# PowerSupply.net
KiCad netlist of a schematic drawn in Altium Designer
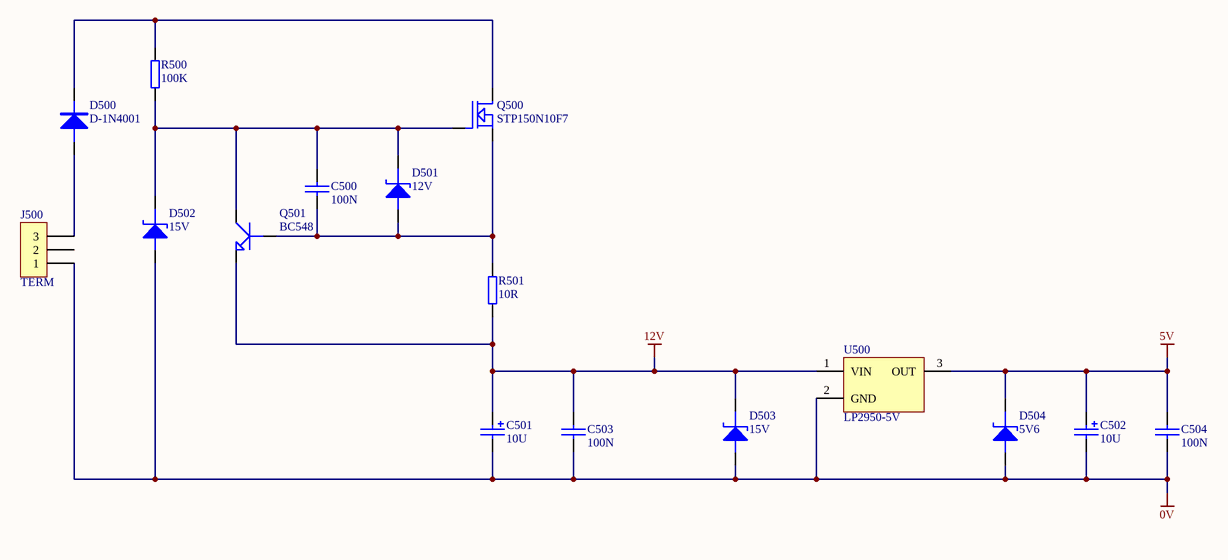
[diagram p0: PowerSupply.SchDoc]

(export (version "E")
  (design (tool "Eeschema 10.0.6"))
  (components
    (comp (ref "C500")
      (value "100N")
      (footprint "AXIAL02")
      (description "CAPACITOR")
      (libsource (lib "SSR") (part "C-B100N"))
    )
    (comp (ref "C501")
      (value "10U")
      (footprint "RADIAL02P")
      (description "CAP")
      (libsource (lib "SSR") (part "C-A10U"))
    )
    (comp (ref "C502")
      (value "10U")
      (footprint "RADIAL02P")
      (description "CAP")
      (libsource (lib "SSR") (part "C-A10U"))
    )
    (comp (ref "C503")
      (value "100N")
      (footprint "AXIAL02")
      (description "CAPACITOR")
      (libsource (lib "SSR") (part "C-B100N"))
    )
    (comp (ref "C504")
      (value "100N")
      (footprint "AXIAL02")
      (description "CAPACITOR")
      (libsource (lib "SSR") (part "C-B100N"))
    )
    (comp (ref "D500")
      (value "D-1N4001")
      (footprint "DO35S")
      (description "1N4001")
      (libsource (lib "SSR") (part "D-1N4001"))
    )
    (comp (ref "D501")
      (value "12V")
      (footprint "DO35S")
      (description "ZENER DIODE")
      (libsource (lib "SSR") (part "D-BZX79-12"))
    )
    (comp (ref "D502")
      (value "15V")
      (footprint "DO35S")
      (description "ZENER DIODE")
      (libsource (lib "SSR") (part "D-BZX79-15"))
    )
    (comp (ref "D503")
      (value "15V")
      (footprint "DO35S")
      (description "ZENER DIODE")
      (libsource (lib "SSR") (part "D-BZX79-15"))
    )
    (comp (ref "D504")
      (value "5V6")
      (footprint "DO35S")
      (description "ZENER DIODE")
      (libsource (lib "SSR") (part "D-BZX79-5V6"))
    )
    (comp (ref "J500")
      (value "TERM")
      (footprint "MKD500S3")
      (description "CONNECTOR")
      (libsource (lib "SSR") (part "J-SCR-3"))
    )
    (comp (ref "Q500")
      (value "STP150N10F7")
      (footprint "TO220FS")
      (description "MOSFET")
      (libsource (lib "SSR") (part "Q-STP150N10F7"))
    )
    (comp (ref "Q501") (value "BC548") (footprint "TO92") (libsource (lib "SSR") (part "Q-BC548")))
    (comp (ref "R500")
      (value "100K")
      (footprint "AXIAL04")
      (description "RESISTOR")
      (libsource (lib "SSR") (part "R-A100K"))
    )
    (comp (ref "R501")
      (value "10R")
      (footprint "AXIAL04")
      (description "RESISTOR")
      (libsource (lib "SSR") (part "R-A10R"))
    )
    (comp (ref "U500")
      (value "LP2950-5V")
      (footprint "TO92")
      (description "LP2950")
      (libsource (lib "SSR") (part "U-LP2950"))
    )
  )
  (nets
    (net (code "1") (name "0V") (class "Default")
      (node (ref "C501") (pin "2") (pinfunction "2_2") (pintype "passive"))
      (node (ref "C502") (pin "2") (pinfunction "2_2") (pintype "passive"))
      (node (ref "C503") (pin "2") (pinfunction "2_2") (pintype "passive"))
      (node (ref "C504") (pin "2") (pinfunction "2_2") (pintype "passive"))
      (node (ref "D502") (pin "1") (pinfunction "A_1") (pintype "passive"))
      (node (ref "D503") (pin "1") (pinfunction "A_1") (pintype "passive"))
      (node (ref "D504") (pin "1") (pinfunction "A_1") (pintype "passive"))
      (node (ref "J500") (pin "1") (pinfunction "1_1") (pintype "passive"))
      (node (ref "U500") (pin "2") (pinfunction "GND_2") (pintype "power_in"))
    )
    (net (code "2") (name "5V") (class "Default")
      (node (ref "C502") (pin "1") (pinfunction "1_1") (pintype "passive"))
      (node (ref "C504") (pin "1") (pinfunction "1_1") (pintype "passive"))
      (node (ref "D504") (pin "2") (pinfunction "K_2") (pintype "passive"))
      (node (ref "U500") (pin "3") (pinfunction "OUT_3") (pintype "passive"))
    )
    (net (code "3") (name "12V") (class "Default")
      (node (ref "C501") (pin "1") (pinfunction "1_1") (pintype "passive"))
      (node (ref "C503") (pin "1") (pinfunction "1_1") (pintype "passive"))
      (node (ref "D503") (pin "2") (pinfunction "K_2") (pintype "passive"))
      (node (ref "Q501") (pin "1") (pinfunction "E_1") (pintype "passive"))
      (node (ref "R501") (pin "1") (pinfunction "1_1") (pintype "passive"))
      (node (ref "U500") (pin "1") (pinfunction "VIN_1") (pintype "passive"))
    )
    (net (code "4") (name "Net-(D500-A)") (class "Default")
      (node (ref "D500") (pin "1") (pinfunction "A_1") (pintype "passive"))
      (node (ref "J500") (pin "3") (pinfunction "3_3") (pintype "passive"))
    )
    (net (code "5") (name "Net-(D500-K)") (class "Default")
      (node (ref "D500") (pin "2") (pinfunction "K_2") (pintype "passive"))
      (node (ref "Q500") (pin "2") (pinfunction "D_2") (pintype "passive"))
      (node (ref "R500") (pin "2") (pinfunction "2_2") (pintype "passive"))
    )
    (net (code "6") (name "Net-(D501-A)") (class "Default")
      (node (ref "C500") (pin "2") (pinfunction "2_2") (pintype "passive"))
      (node (ref "D501") (pin "1") (pinfunction "A_1") (pintype "passive"))
      (node (ref "Q500") (pin "3") (pinfunction "S_3") (pintype "passive"))
      (node (ref "Q501") (pin "2") (pinfunction "B_2") (pintype "passive"))
      (node (ref "R501") (pin "2") (pinfunction "2_2") (pintype "passive"))
    )
    (net (code "7") (name "Net-(D501-K)") (class "Default")
      (node (ref "C500") (pin "1") (pinfunction "1_1") (pintype "passive"))
      (node (ref "D501") (pin "2") (pinfunction "K_2") (pintype "passive"))
      (node (ref "D502") (pin "2") (pinfunction "K_2") (pintype "passive"))
      (node (ref "Q500") (pin "1") (pinfunction "G_1") (pintype "passive"))
      (node (ref "Q501") (pin "3") (pinfunction "C_3") (pintype "passive"))
      (node (ref "R500") (pin "1") (pinfunction "1_1") (pintype "passive"))
    )
    (net (code "8") (name "unconnected-(J500-Pad2)") (class "Default")
      (node (ref "J500") (pin "2") (pinfunction "2_2") (pintype "passive"))
    )
  )
)
